# RC_Connections.net
KiCad netlist of a schematic drawn in Altium Designer
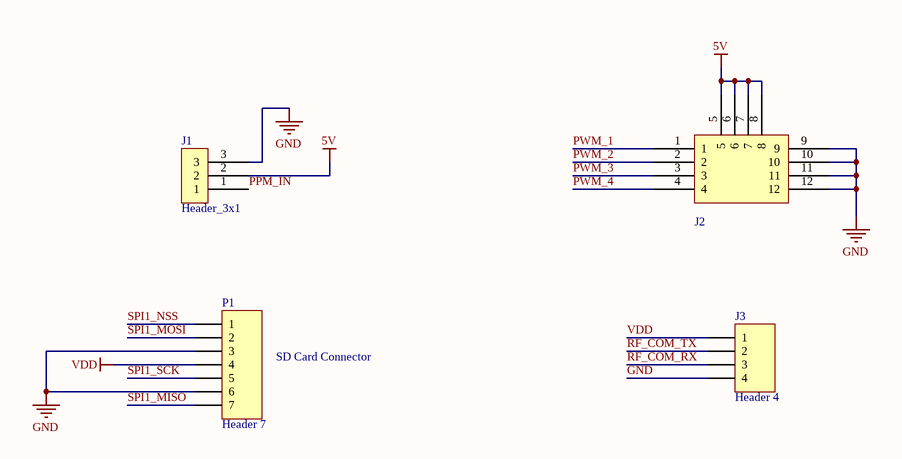
[diagram p0: RC_Connections.SchDoc]

(export (version "E")
  (design (tool "Eeschema 10.0.6"))
  (components
    (comp (ref "J1") (value "Header_3x1") (footprint "Header_3x1") (libsource (lib "FC") (part "Header_3x1")))
    (comp (ref "J2") (value "Header 4x3") (footprint "Header_4x3") (libsource (lib "FC") (part "Header_4x3")))
    (comp (ref "J3")
      (value "Header 4")
      (footprint "HDR1X4")
      (description "Header, 4-Pin")
      (fields (field (name "PUBLISHER") "Altium Limited"))
      (libsource (lib "Connectors and Headers") (part "Header 4"))
    )
    (comp (ref "P1")
      (value "Header 7")
      (footprint "HDR1X7")
      (description "Header, 7-Pin")
      (fields (field (name "PUBLISHER") "Altium Limited"))
      (libsource (lib "Connectors and Headers") (part "Header 7"))
    )
  )
  (nets
    (net (code "1") (name "/PPM_IN") (class "Default")
      (node (ref "J1") (pin "1") (pinfunction "1_1") (pintype "power_in"))
    )
    (net (code "2") (name "/PWM_1") (class "Default")
      (node (ref "J2") (pin "1") (pinfunction "1_1") (pintype "power_in"))
    )
    (net (code "3") (name "/PWM_2") (class "Default")
      (node (ref "J2") (pin "2") (pinfunction "2_2") (pintype "power_in"))
    )
    (net (code "4") (name "/PWM_3") (class "Default")
      (node (ref "J2") (pin "3") (pinfunction "3_3") (pintype "power_in"))
    )
    (net (code "5") (name "/PWM_4") (class "Default")
      (node (ref "J2") (pin "4") (pinfunction "4_4") (pintype "power_in"))
    )
    (net (code "6") (name "/RF_COM_RX") (class "Default")
      (node (ref "J3") (pin "3") (pinfunction "3_3") (pintype "passive"))
    )
    (net (code "7") (name "/RF_COM_TX") (class "Default")
      (node (ref "J3") (pin "2") (pinfunction "2_2") (pintype "passive"))
    )
    (net (code "8") (name "/SPI1_MISO") (class "Default")
      (node (ref "P1") (pin "7") (pinfunction "7_7") (pintype "passive"))
    )
    (net (code "9") (name "/SPI1_MOSI") (class "Default")
      (node (ref "P1") (pin "2") (pinfunction "2_2") (pintype "passive"))
    )
    (net (code "10") (name "/SPI1_NSS") (class "Default")
      (node (ref "P1") (pin "1") (pinfunction "1_1") (pintype "passive"))
    )
    (net (code "11") (name "/SPI1_SCK") (class "Default")
      (node (ref "P1") (pin "5") (pinfunction "5_5") (pintype "passive"))
    )
    (net (code "12") (name "5V") (class "Default")
      (node (ref "J1") (pin "2") (pinfunction "2_2") (pintype "power_in"))
      (node (ref "J2") (pin "5") (pinfunction "5_5") (pintype "power_in"))
      (node (ref "J2") (pin "6") (pinfunction "6_6") (pintype "power_in"))
      (node (ref "J2") (pin "7") (pinfunction "7_7") (pintype "power_in"))
      (node (ref "J2") (pin "8") (pinfunction "8_8") (pintype "power_in"))
    )
    (net (code "13") (name "GND") (class "Default")
      (node (ref "J1") (pin "3") (pinfunction "3_3") (pintype "power_in"))
      (node (ref "J2") (pin "10") (pinfunction "10_10") (pintype "power_in"))
      (node (ref "J2") (pin "11") (pinfunction "11_11") (pintype "power_in"))
      (node (ref "J2") (pin "12") (pinfunction "12_12") (pintype "power_in"))
      (node (ref "J2") (pin "9") (pinfunction "9_9") (pintype "power_in"))
      (node (ref "J3") (pin "4") (pinfunction "4_4") (pintype "passive"))
      (node (ref "P1") (pin "3") (pinfunction "3_3") (pintype "passive"))
      (node (ref "P1") (pin "6") (pinfunction "6_6") (pintype "passive"))
    )
    (net (code "14") (name "VDD") (class "Default")
      (node (ref "J3") (pin "1") (pinfunction "1_1") (pintype "passive"))
      (node (ref "P1") (pin "4") (pinfunction "4_4") (pintype "passive"))
    )
  )
)
